# doorbell.net
KiCad netlist of a schematic drawn in EAGLE
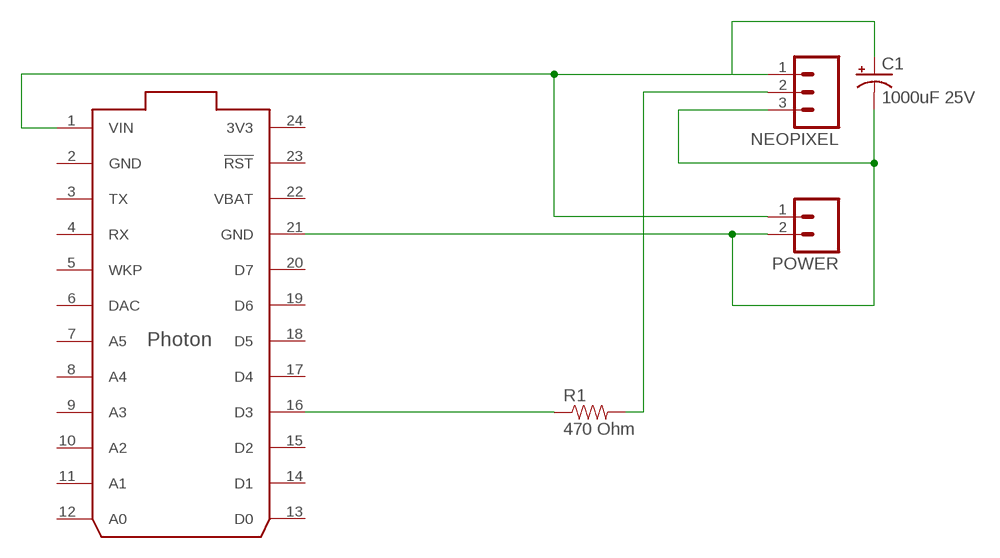
[diagram p0: schematic, sheet 1]

(export (version "E")
  (design (tool "Eeschema 10.0.6"))
  (components
    (comp (ref "C1")
      (value "1000uF 25V")
      (footprint "eagle-import:CPOL-RADIAL-1000UF-25V")
      (libsource (lib "eagle-import") (part "1000UF-25V(PTH)"))
    )
    (comp (ref "NEOPIXEL")
      (value "M03LONGPADS")
      (footprint "eagle-import:1X03_LONGPADS")
      (libsource (lib "eagle-import") (part "M03LONGPADS"))
    )
    (comp (ref "POWER")
      (value "M02POGO_PIN_HOLES_ONLY")
      (footprint "eagle-import:1X02_PP_HOLES_ONLY")
      (libsource (lib "eagle-import") (part "M02POGO_PIN_HOLES_ONLY"))
    )
    (comp (ref "R1")
      (value "470 Ohm")
      (footprint "eagle-import:AXIAL-0.3")
      (libsource (lib "eagle-import") (part "RESISTORAXIAL-0.3"))
    )
    (comp (ref "U$1")
      (value "PHOTON_SMD")
      (footprint "eagle-import:PHOTON_SMD")
      (libsource (lib "eagle-import") (part "PHOTON_SMD"))
    )
  )
  (nets
    (net (code "1") (name "/3V3") (class "Default")
      (node (ref "U$1") (pin "24") (pinfunction "3V3_24") (pintype "power_in"))
    )
    (net (code "2") (name "/GND") (class "Default")
      (node (ref "U$1") (pin "2") (pinfunction "GND_2") (pintype "power_in"))
    )
    (net (code "3") (name "/VBAT") (class "Default")
      (node (ref "U$1") (pin "22") (pinfunction "VBAT_22") (pintype "power_in"))
    )
    (net (code "4") (name "Net-(C1-Pad-)") (class "Default")
      (node (ref "C1") (pin "-") (pinfunction "-_-") (pintype "passive"))
      (node (ref "NEOPIXEL") (pin "3") (pinfunction "3_3") (pintype "passive"))
      (node (ref "POWER") (pin "2") (pinfunction "2_2") (pintype "passive"))
      (node (ref "U$1") (pin "21") (pinfunction "GND_21") (pintype "power_in"))
    )
    (net (code "5") (name "Net-(R1-1)") (class "Default")
      (node (ref "R1") (pin "P$1") (pinfunction "1_P$1") (pintype "passive"))
      (node (ref "U$1") (pin "16") (pinfunction "D3_16") (pintype "bidirectional"))
    )
    (net (code "6") (name "Net-(R1-2)") (class "Default")
      (node (ref "NEOPIXEL") (pin "2") (pinfunction "2_2") (pintype "passive"))
      (node (ref "R1") (pin "P$2") (pinfunction "2_P$2") (pintype "passive"))
    )
    (net (code "7") (name "Net-(U$1A-VIN)") (class "Default")
      (node (ref "C1") (pin "+") (pinfunction "+_+") (pintype "passive"))
      (node (ref "NEOPIXEL") (pin "1") (pinfunction "1_1") (pintype "passive"))
      (node (ref "POWER") (pin "1") (pinfunction "1_1") (pintype "passive"))
      (node (ref "U$1") (pin "1") (pinfunction "VIN_1") (pintype "power_in"))
    )
    (net (code "8") (name "unconnected-(U$1A-A0-Pad12)") (class "Default")
      (node (ref "U$1") (pin "12") (pinfunction "A0_12") (pintype "bidirectional"))
    )
    (net (code "9") (name "unconnected-(U$1A-A1-Pad11)") (class "Default")
      (node (ref "U$1") (pin "11") (pinfunction "A1_11") (pintype "bidirectional"))
    )
    (net (code "10") (name "unconnected-(U$1A-A2-Pad10)") (class "Default")
      (node (ref "U$1") (pin "10") (pinfunction "A2_10") (pintype "bidirectional"))
    )
    (net (code "11") (name "unconnected-(U$1A-A3-Pad9)") (class "Default")
      (node (ref "U$1") (pin "9") (pinfunction "A3_9") (pintype "bidirectional"))
    )
    (net (code "12") (name "unconnected-(U$1A-A4-Pad8)") (class "Default")
      (node (ref "U$1") (pin "8") (pinfunction "A4_8") (pintype "bidirectional"))
    )
    (net (code "13") (name "unconnected-(U$1A-A5-Pad7)") (class "Default")
      (node (ref "U$1") (pin "7") (pinfunction "A5_7") (pintype "bidirectional"))
    )
    (net (code "14") (name "unconnected-(U$1A-D0-Pad13)") (class "Default")
      (node (ref "U$1") (pin "13") (pinfunction "D0_13") (pintype "bidirectional"))
    )
    (net (code "15") (name "unconnected-(U$1A-D1-Pad14)") (class "Default")
      (node (ref "U$1") (pin "14") (pinfunction "D1_14") (pintype "bidirectional"))
    )
    (net (code "16") (name "unconnected-(U$1A-D2-Pad15)") (class "Default")
      (node (ref "U$1") (pin "15") (pinfunction "D2_15") (pintype "bidirectional"))
    )
    (net (code "17") (name "unconnected-(U$1A-D4-Pad17)") (class "Default")
      (node (ref "U$1") (pin "17") (pinfunction "D4_17") (pintype "bidirectional"))
    )
    (net (code "18") (name "unconnected-(U$1A-D5-Pad18)") (class "Default")
      (node (ref "U$1") (pin "18") (pinfunction "D5_18") (pintype "bidirectional"))
    )
    (net (code "19") (name "unconnected-(U$1A-D6-Pad19)") (class "Default")
      (node (ref "U$1") (pin "19") (pinfunction "D6_19") (pintype "bidirectional"))
    )
    (net (code "20") (name "unconnected-(U$1A-D7-Pad20)") (class "Default")
      (node (ref "U$1") (pin "20") (pinfunction "D7_20") (pintype "bidirectional"))
    )
    (net (code "21") (name "unconnected-(U$1A-DAC-Pad6)") (class "Default")
      (node (ref "U$1") (pin "6") (pinfunction "DAC_6") (pintype "bidirectional"))
    )
    (net (code "22") (name "unconnected-(U$1A-RX-Pad4)") (class "Default")
      (node (ref "U$1") (pin "4") (pinfunction "RX_4") (pintype "bidirectional"))
    )
    (net (code "23") (name "unconnected-(U$1A-TX-Pad3)") (class "Default")
      (node (ref "U$1") (pin "3") (pinfunction "TX_3") (pintype "bidirectional"))
    )
    (net (code "24") (name "unconnected-(U$1A-WKP-Pad5)") (class "Default")
      (node (ref "U$1") (pin "5") (pinfunction "WKP_5") (pintype "bidirectional"))
    )
    (net (code "25") (name "unconnected-(U$1A-~{RST}-Pad23)") (class "Default")
      (node (ref "U$1") (pin "23") (pinfunction "~{RST}_23") (pintype "bidirectional"))
    )
  )
)
